# nanoDimmerTouchPad.net
KiCad netlist of a schematic drawn in EAGLE
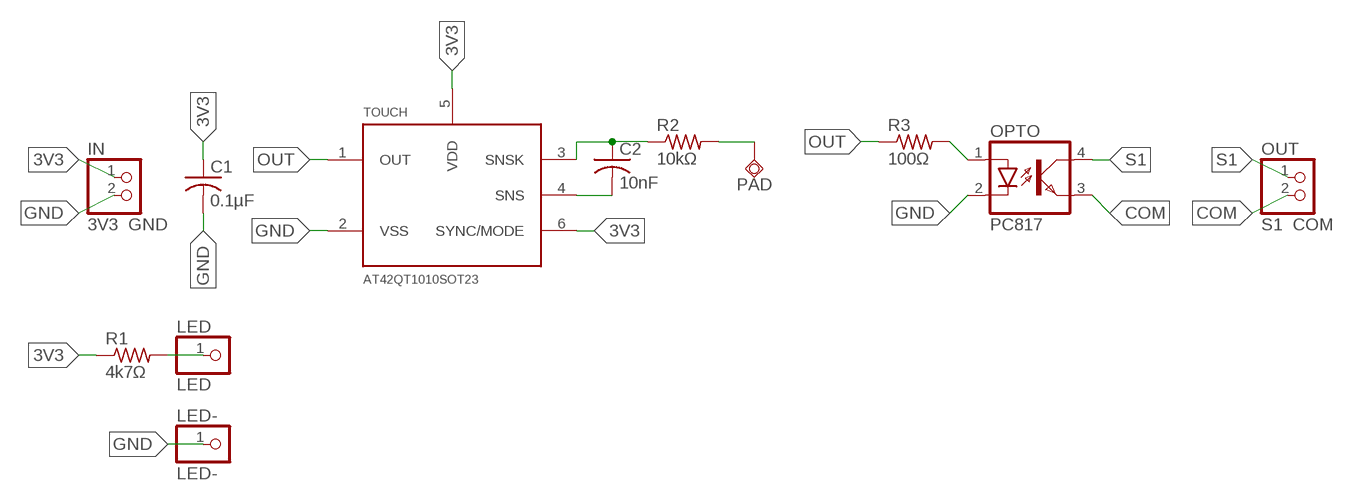
[diagram p0: schematic, sheet 1]

(export (version "E")
  (design (tool "Eeschema 10.0.6"))
  (components
    (comp (ref "C1")
      (value "0.1µF")
      (footprint "eagle-import:C1206")
      (libsource (lib "eagle-import") (part "C-USC1206"))
    )
    (comp (ref "C2")
      (value "10nF")
      (footprint "eagle-import:C1206")
      (libsource (lib "eagle-import") (part "C-USC1206"))
    )
    (comp (ref "IN")
      (value "3V3 GND")
      (footprint "eagle-import:1X02")
      (libsource (lib "eagle-import") (part "PINHD-1X2"))
    )
    (comp (ref "LED")
      (value "LED")
      (footprint "eagle-import:1X01")
      (libsource (lib "eagle-import") (part "PINHD-1X1"))
    )
    (comp (ref "LED-")
      (value "LED-")
      (footprint "eagle-import:1X01")
      (libsource (lib "eagle-import") (part "PINHD-1X1"))
    )
    (comp (ref "OPTO")
      (value "PC817")
      (footprint "eagle-import:DIL04")
      (fields (field (name "MPN") "PC817X4J000F"))
      (libsource (lib "eagle-import") (part "PC817"))
    )
    (comp (ref "OUT")
      (value "S1 COM")
      (footprint "eagle-import:1X02")
      (libsource (lib "eagle-import") (part "PINHD-1X2"))
    )
    (comp (ref "PAD")
      (value "TPSQPAD1-13")
      (footprint "eagle-import:P1-13")
      (libsource (lib "eagle-import") (part "TPSQPAD1-13"))
    )
    (comp (ref "R1")
      (value "4k7Ω")
      (footprint "eagle-import:R1206")
      (libsource (lib "eagle-import") (part "R-US_R1206"))
    )
    (comp (ref "R2")
      (value "10kΩ")
      (footprint "eagle-import:R1206")
      (libsource (lib "eagle-import") (part "R-US_R1206"))
    )
    (comp (ref "R3")
      (value "100Ω")
      (footprint "eagle-import:R1206")
      (libsource (lib "eagle-import") (part "R-US_R1206"))
    )
    (comp (ref "TOUCH")
      (value "AT42QT1010SOT23")
      (footprint "eagle-import:SOT23-6")
      (libsource (lib "eagle-import") (part "AT42QT1010SOT23"))
    )
  )
  (nets
    (net (code "1") (name "3V3") (class "Default")
      (node (ref "C1") (pin "1") (pinfunction "1_1") (pintype "passive"))
      (node (ref "IN") (pin "1") (pinfunction "1_1") (pintype "passive"))
      (node (ref "R1") (pin "1") (pinfunction "1_1") (pintype "passive"))
      (node (ref "TOUCH") (pin "5") (pinfunction "VDD_5") (pintype "bidirectional"))
      (node (ref "TOUCH") (pin "6") (pinfunction "SYNC/MODE_6") (pintype "bidirectional"))
    )
    (net (code "2") (name "COM") (class "Default")
      (node (ref "OPTO") (pin "3") (pinfunction "EMIT_3") (pintype "passive"))
      (node (ref "OUT") (pin "2") (pinfunction "2_2") (pintype "passive"))
    )
    (net (code "3") (name "GND") (class "Default")
      (node (ref "C1") (pin "2") (pinfunction "2_2") (pintype "passive"))
      (node (ref "IN") (pin "2") (pinfunction "2_2") (pintype "passive"))
      (node (ref "LED-") (pin "1") (pinfunction "1_1") (pintype "passive"))
      (node (ref "OPTO") (pin "2") (pinfunction "C_2") (pintype "passive"))
      (node (ref "TOUCH") (pin "2") (pinfunction "VSS_2") (pintype "bidirectional"))
    )
    (net (code "4") (name "Net-(LED-Pad1)") (class "Default")
      (node (ref "LED") (pin "1") (pinfunction "1_1") (pintype "passive"))
      (node (ref "R1") (pin "2") (pinfunction "2_2") (pintype "passive"))
    )
    (net (code "5") (name "Net-(OPTO-A)") (class "Default")
      (node (ref "OPTO") (pin "1") (pinfunction "A_1") (pintype "passive"))
      (node (ref "R3") (pin "2") (pinfunction "2_2") (pintype "passive"))
    )
    (net (code "6") (name "Net-(PAD-PadTP)") (class "Default")
      (node (ref "PAD") (pin "TP") (pinfunction "TP_TP") (pintype "input"))
      (node (ref "R2") (pin "2") (pinfunction "2_2") (pintype "passive"))
    )
    (net (code "7") (name "Net-(TOUCH-SNS)") (class "Default")
      (node (ref "C2") (pin "2") (pinfunction "2_2") (pintype "passive"))
      (node (ref "TOUCH") (pin "4") (pinfunction "SNS_4") (pintype "bidirectional"))
    )
    (net (code "8") (name "Net-(TOUCH-SNSK)") (class "Default")
      (node (ref "C2") (pin "1") (pinfunction "1_1") (pintype "passive"))
      (node (ref "R2") (pin "1") (pinfunction "1_1") (pintype "passive"))
      (node (ref "TOUCH") (pin "3") (pinfunction "SNSK_3") (pintype "bidirectional"))
    )
    (net (code "9") (name "OUT") (class "Default")
      (node (ref "R3") (pin "1") (pinfunction "1_1") (pintype "passive"))
      (node (ref "TOUCH") (pin "1") (pinfunction "OUT_1") (pintype "bidirectional"))
    )
    (net (code "10") (name "S1") (class "Default")
      (node (ref "OPTO") (pin "4") (pinfunction "COL_4") (pintype "passive"))
      (node (ref "OUT") (pin "1") (pinfunction "1_1") (pintype "passive"))
    )
  )
)
